# Sheet6.net
KiCad netlist of a schematic drawn in Altium Designer
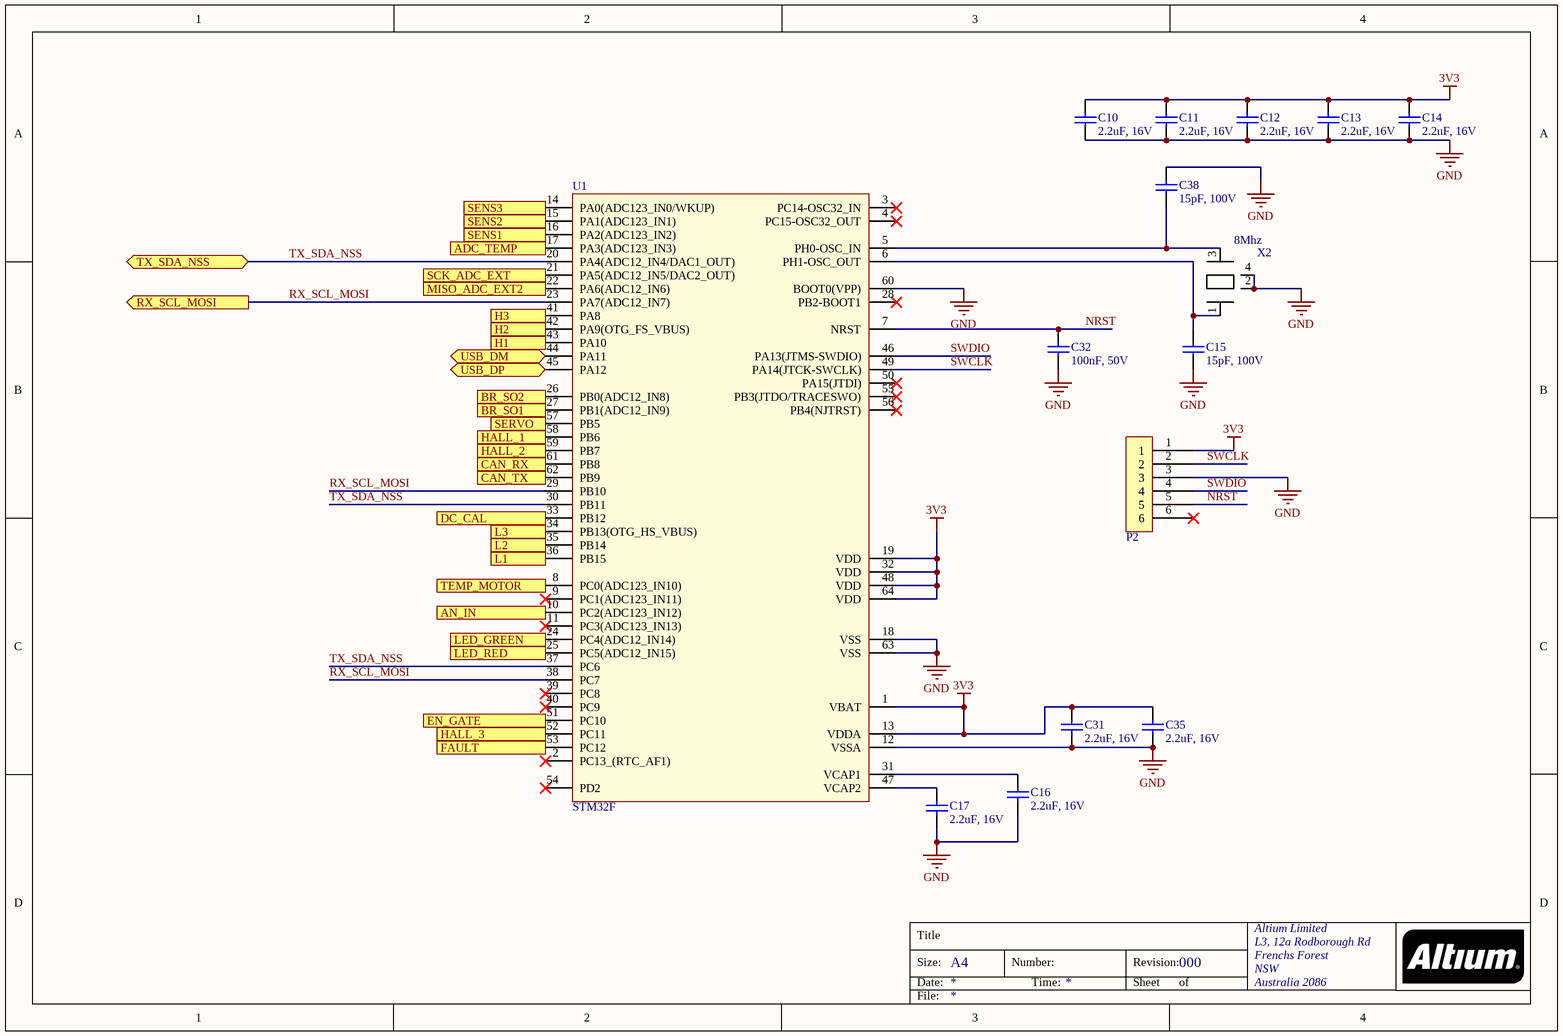
[diagram p0: Sheet6.SchDoc]

(export (version "E")
  (design (tool "Eeschema 10.0.6"))
  (components
    (comp (ref "C10")
      (value "2.2uF, 16V")
      (footprint "SMD-0603 Capacitor")
      (description "CAP 2.2u, 16V, 0603")
      (fields
        (field (name "MANUFACTURER PART NUMBER") "C1608X5R1C225M")
        (field (name "MANUFACTURER") "TDK Corporation")
      )
      (libsource (lib "Master Data Link") (part "CAP"))
    )
    (comp (ref "C11")
      (value "2.2uF, 16V")
      (footprint "SMD-0603 Capacitor")
      (description "CAP 2.2u, 16V, 0603")
      (fields
        (field (name "MANUFACTURER PART NUMBER") "C1608X5R1C225M")
        (field (name "MANUFACTURER") "TDK Corporation")
      )
      (libsource (lib "Master Data Link") (part "CAP"))
    )
    (comp (ref "C12")
      (value "2.2uF, 16V")
      (footprint "SMD-0603 Capacitor")
      (description "CAP 2.2u, 16V, 0603")
      (fields
        (field (name "MANUFACTURER PART NUMBER") "C1608X5R1C225M")
        (field (name "MANUFACTURER") "TDK Corporation")
      )
      (libsource (lib "Master Data Link") (part "CAP"))
    )
    (comp (ref "C13")
      (value "2.2uF, 16V")
      (footprint "SMD-0603 Capacitor")
      (description "CAP 2.2u, 16V, 0603")
      (fields
        (field (name "MANUFACTURER PART NUMBER") "C1608X5R1C225M")
        (field (name "MANUFACTURER") "TDK Corporation")
      )
      (libsource (lib "Master Data Link") (part "CAP"))
    )
    (comp (ref "C14")
      (value "2.2uF, 16V")
      (footprint "SMD-0603 Capacitor")
      (description "CAP 2.2u, 16V, 0603")
      (fields
        (field (name "MANUFACTURER PART NUMBER") "C1608X5R1C225M")
        (field (name "MANUFACTURER") "TDK Corporation")
      )
      (libsource (lib "Master Data Link") (part "CAP"))
    )
    (comp (ref "C15")
      (value "15pF, 100V")
      (footprint "SMD-0603 Capacitor")
      (description "CAP 15p, 100V, 0603")
      (fields
        (field (name "MANUFACTURER PART NUMBER") "GRM1885C2A150JA01")
        (field (name "MANUFACTURER") "Murata Electronics North America")
      )
      (libsource (lib "Master Data Link") (part "CAP"))
    )
    (comp (ref "C16")
      (value "2.2uF, 16V")
      (footprint "SMD-0603 Capacitor")
      (description "CAP 2.2u, 16V, 0603")
      (fields
        (field (name "MANUFACTURER PART NUMBER") "C1608X5R1C225M")
        (field (name "MANUFACTURER") "TDK Corporation")
      )
      (libsource (lib "Master Data Link") (part "CAP"))
    )
    (comp (ref "C17")
      (value "2.2uF, 16V")
      (footprint "SMD-0603 Capacitor")
      (description "CAP 2.2u, 16V, 0603")
      (fields
        (field (name "MANUFACTURER PART NUMBER") "C1608X5R1C225M")
        (field (name "MANUFACTURER") "TDK Corporation")
      )
      (libsource (lib "Master Data Link") (part "CAP"))
    )
    (comp (ref "C31")
      (value "2.2uF, 16V")
      (footprint "SMD-0603 Capacitor")
      (description "CAP 2.2u, 16V, 0603")
      (fields
        (field (name "MANUFACTURER PART NUMBER") "C1608X5R1C225M")
        (field (name "MANUFACTURER") "TDK Corporation")
      )
      (libsource (lib "Master Data Link") (part "CAP"))
    )
    (comp (ref "C32")
      (value "100nF, 50V")
      (footprint "SMD-0603 Capacitor")
      (description "CAP 100n, 50V, 0603")
      (fields
        (field (name "MANUFACTURER PART NUMBER") "06035C104JAT2A")
        (field (name "MANUFACTURER") "AVX Corporation")
      )
      (libsource (lib "Master Data Link") (part "CAP"))
    )
    (comp (ref "C35")
      (value "2.2uF, 16V")
      (footprint "SMD-0603 Capacitor")
      (description "CAP 2.2u, 16V, 0603")
      (fields
        (field (name "MANUFACTURER PART NUMBER") "C1608X5R1C225M")
        (field (name "MANUFACTURER") "TDK Corporation")
      )
      (libsource (lib "Master Data Link") (part "CAP"))
    )
    (comp (ref "C38")
      (value "15pF, 100V")
      (footprint "SMD-0603 Capacitor")
      (description "CAP 15p, 100V, 0603")
      (fields
        (field (name "MANUFACTURER PART NUMBER") "GRM1885C2A150JA01")
        (field (name "MANUFACTURER") "Murata Electronics North America")
      )
      (libsource (lib "Master Data Link") (part "CAP"))
    )
    (comp (ref "P2")
      (value "B6B-PH-K-S(LF)(SN)")
      (footprint "JST PH TH VERT 6")
      (description "JST PH Through hole Vertical 6 Pin")
      (fields (field (name "MANUFACTURER") "JST"))
      (libsource (lib "Master Data Link") (part "CON6"))
    )
    (comp (ref "U1")
      (value "STM32F")
      (footprint "TSQFP50P1200X1200X160-64")
      (description "IC MCU 32BIT 1MB FLASH 64LQFP")
      (fields
        (field (name "MANUFACTURER PART NUMBER") "STM32F405RGT6")
        (field (name "MANUFACTURER") "STMicroelectronics")
      )
      (libsource (lib "Master Data Link") (part "STM32F"))
    )
    (comp (ref "X2")
      (value "8Mhz")
      (footprint "4-SMD CRYSTAL 5X3.2mm")
      (description "Crystal 8MHz, 10PPM")
      (fields
        (field (name "MANUFACTURER PART NUMBER") "ABM3B-8.0-10-1UT")
        (field (name "MANUFACTURER") "Abracon LLC")
      )
      (libsource (lib "Master Data Link") (part "OSC_1"))
    )
  )
  (nets
    (net (code "1") (name "/ADC_TEMP") (class "Default")
      (node (ref "U1") (pin "17") (pinfunction "PA3(ADC123_IN3)_17") (pintype "passive"))
    )
    (net (code "2") (name "/AN_IN") (class "Default")
      (node (ref "U1") (pin "10") (pinfunction "PC2(ADC123_IN12)_10") (pintype "passive"))
    )
    (net (code "3") (name "/BR_SO1") (class "Default")
      (node (ref "U1") (pin "27") (pinfunction "PB1(ADC12_IN9)_27") (pintype "passive"))
    )
    (net (code "4") (name "/BR_SO2") (class "Default")
      (node (ref "U1") (pin "26") (pinfunction "PB0(ADC12_IN8)_26") (pintype "passive"))
    )
    (net (code "5") (name "/CAN_RX") (class "Default")
      (node (ref "U1") (pin "61") (pinfunction "PB8_61") (pintype "passive"))
    )
    (net (code "6") (name "/CAN_TX") (class "Default")
      (node (ref "U1") (pin "62") (pinfunction "PB9_62") (pintype "passive"))
    )
    (net (code "7") (name "/DC_CAL") (class "Default")
      (node (ref "U1") (pin "33") (pinfunction "PB12_33") (pintype "passive"))
    )
    (net (code "8") (name "/EN_GATE") (class "Default")
      (node (ref "U1") (pin "51") (pinfunction "PC10_51") (pintype "passive"))
    )
    (net (code "9") (name "/FAULT") (class "Default")
      (node (ref "U1") (pin "53") (pinfunction "PC12_53") (pintype "passive"))
    )
    (net (code "10") (name "/H1") (class "Default")
      (node (ref "U1") (pin "43") (pinfunction "PA10_43") (pintype "passive"))
    )
    (net (code "11") (name "/H2") (class "Default")
      (node (ref "U1") (pin "42") (pinfunction "PA9(OTG_FS_VBUS)_42") (pintype "passive"))
    )
    (net (code "12") (name "/H3") (class "Default")
      (node (ref "U1") (pin "41") (pinfunction "PA8_41") (pintype "passive"))
    )
    (net (code "13") (name "/HALL_1") (class "Default")
      (node (ref "U1") (pin "58") (pinfunction "PB6_58") (pintype "passive"))
    )
    (net (code "14") (name "/HALL_2") (class "Default")
      (node (ref "U1") (pin "59") (pinfunction "PB7_59") (pintype "passive"))
    )
    (net (code "15") (name "/HALL_3") (class "Default")
      (node (ref "U1") (pin "52") (pinfunction "PC11_52") (pintype "passive"))
    )
    (net (code "16") (name "/L1") (class "Default")
      (node (ref "U1") (pin "36") (pinfunction "PB15_36") (pintype "passive"))
    )
    (net (code "17") (name "/L2") (class "Default")
      (node (ref "U1") (pin "35") (pinfunction "PB14_35") (pintype "passive"))
    )
    (net (code "18") (name "/L3") (class "Default")
      (node (ref "U1") (pin "34") (pinfunction "PB13(OTG_HS_VBUS)_34") (pintype "passive"))
    )
    (net (code "19") (name "/LED_GREEN") (class "Default")
      (node (ref "U1") (pin "24") (pinfunction "PC4(ADC12_IN14)_24") (pintype "passive"))
    )
    (net (code "20") (name "/LED_RED") (class "Default")
      (node (ref "U1") (pin "25") (pinfunction "PC5(ADC12_IN15)_25") (pintype "passive"))
    )
    (net (code "21") (name "/MISO_ADC_EXT2") (class "Default")
      (node (ref "U1") (pin "22") (pinfunction "PA6(ADC12_IN6)_22") (pintype "passive"))
    )
    (net (code "22") (name "/NRST") (class "Default")
      (node (ref "C32") (pin "2") (pinfunction "2_2") (pintype "passive"))
      (node (ref "P2") (pin "5") (pinfunction "5_5") (pintype "passive"))
      (node (ref "U1") (pin "7") (pinfunction "NRST_7") (pintype "passive"))
    )
    (net (code "23") (name "/RX_SCL_MOSI") (class "Default")
      (node (ref "U1") (pin "23") (pinfunction "PA7(ADC12_IN7)_23") (pintype "passive"))
      (node (ref "U1") (pin "29") (pinfunction "PB10_29") (pintype "passive"))
      (node (ref "U1") (pin "38") (pinfunction "PC7_38") (pintype "passive"))
    )
    (net (code "24") (name "/SCK_ADC_EXT") (class "Default")
      (node (ref "U1") (pin "21") (pinfunction "PA5(ADC12_IN5/DAC2_OUT)_21") (pintype "passive"))
    )
    (net (code "25") (name "/SENS1") (class "Default")
      (node (ref "U1") (pin "16") (pinfunction "PA2(ADC123_IN2)_16") (pintype "passive"))
    )
    (net (code "26") (name "/SENS2") (class "Default")
      (node (ref "U1") (pin "15") (pinfunction "PA1(ADC123_IN1)_15") (pintype "passive"))
    )
    (net (code "27") (name "/SENS3") (class "Default")
      (node (ref "U1") (pin "14") (pinfunction "PA0(ADC123_IN0/WKUP)_14") (pintype "passive"))
    )
    (net (code "28") (name "/SERVO") (class "Default")
      (node (ref "U1") (pin "57") (pinfunction "PB5_57") (pintype "passive"))
    )
    (net (code "29") (name "/SWCLK") (class "Default")
      (node (ref "P2") (pin "2") (pinfunction "2_2") (pintype "passive"))
      (node (ref "U1") (pin "49") (pinfunction "PA14(JTCK-SWCLK)_49") (pintype "passive"))
    )
    (net (code "30") (name "/SWDIO") (class "Default")
      (node (ref "P2") (pin "4") (pinfunction "4_4") (pintype "passive"))
      (node (ref "U1") (pin "46") (pinfunction "PA13(JTMS-SWDIO)_46") (pintype "passive"))
    )
    (net (code "31") (name "/TEMP_MOTOR") (class "Default")
      (node (ref "U1") (pin "8") (pinfunction "PC0(ADC123_IN10)_8") (pintype "passive"))
    )
    (net (code "32") (name "/TX_SDA_NSS") (class "Default")
      (node (ref "U1") (pin "20") (pinfunction "PA4(ADC12_IN4/DAC1_OUT)_20") (pintype "passive"))
      (node (ref "U1") (pin "30") (pinfunction "PB11_30") (pintype "passive"))
      (node (ref "U1") (pin "37") (pinfunction "PC6_37") (pintype "passive"))
    )
    (net (code "33") (name "/USB_DM") (class "Default")
      (node (ref "U1") (pin "44") (pinfunction "PA11_44") (pintype "passive"))
    )
    (net (code "34") (name "/USB_DP") (class "Default")
      (node (ref "U1") (pin "45") (pinfunction "PA12_45") (pintype "passive"))
    )
    (net (code "35") (name "3V3") (class "Default")
      (node (ref "C10") (pin "2") (pinfunction "2_2") (pintype "passive"))
      (node (ref "C11") (pin "2") (pinfunction "2_2") (pintype "passive"))
      (node (ref "C12") (pin "2") (pinfunction "2_2") (pintype "passive"))
      (node (ref "C13") (pin "2") (pinfunction "2_2") (pintype "passive"))
      (node (ref "C14") (pin "2") (pinfunction "2_2") (pintype "passive"))
      (node (ref "C31") (pin "2") (pinfunction "2_2") (pintype "passive"))
      (node (ref "C35") (pin "2") (pinfunction "2_2") (pintype "passive"))
      (node (ref "P2") (pin "1") (pinfunction "1_1") (pintype "passive"))
      (node (ref "U1") (pin "1") (pinfunction "VBAT_1") (pintype "passive"))
      (node (ref "U1") (pin "13") (pinfunction "VDDA_13") (pintype "passive"))
      (node (ref "U1") (pin "19") (pinfunction "VDD_19") (pintype "passive"))
      (node (ref "U1") (pin "32") (pinfunction "VDD_32") (pintype "passive"))
      (node (ref "U1") (pin "48") (pinfunction "VDD_48") (pintype "passive"))
      (node (ref "U1") (pin "64") (pinfunction "VDD_64") (pintype "passive"))
    )
    (net (code "36") (name "GND") (class "Default")
      (node (ref "C10") (pin "1") (pinfunction "1_1") (pintype "passive"))
      (node (ref "C11") (pin "1") (pinfunction "1_1") (pintype "passive"))
      (node (ref "C12") (pin "1") (pinfunction "1_1") (pintype "passive"))
      (node (ref "C13") (pin "1") (pinfunction "1_1") (pintype "passive"))
      (node (ref "C14") (pin "1") (pinfunction "1_1") (pintype "passive"))
      (node (ref "C15") (pin "1") (pinfunction "1_1") (pintype "passive"))
      (node (ref "C16") (pin "1") (pinfunction "1_1") (pintype "passive"))
      (node (ref "C17") (pin "1") (pinfunction "1_1") (pintype "passive"))
      (node (ref "C31") (pin "1") (pinfunction "1_1") (pintype "passive"))
      (node (ref "C32") (pin "1") (pinfunction "1_1") (pintype "passive"))
      (node (ref "C35") (pin "1") (pinfunction "1_1") (pintype "passive"))
      (node (ref "C38") (pin "2") (pinfunction "2_2") (pintype "passive"))
      (node (ref "P2") (pin "3") (pinfunction "3_3") (pintype "passive"))
      (node (ref "U1") (pin "12") (pinfunction "VSSA_12") (pintype "passive"))
      (node (ref "U1") (pin "18") (pinfunction "VSS_18") (pintype "passive"))
      (node (ref "U1") (pin "60") (pinfunction "BOOT0(VPP)_60") (pintype "passive"))
      (node (ref "U1") (pin "63") (pinfunction "VSS_63") (pintype "passive"))
      (node (ref "X2") (pin "2") (pinfunction "3_2") (pintype "passive"))
      (node (ref "X2") (pin "4") (pinfunction "4_4") (pintype "passive"))
    )
    (net (code "37") (name "Net-(U1-PH0-OSC_IN)") (class "Default")
      (node (ref "C38") (pin "1") (pinfunction "1_1") (pintype "passive"))
      (node (ref "U1") (pin "5") (pinfunction "PH0-OSC_IN_5") (pintype "passive"))
      (node (ref "X2") (pin "3") (pinfunction "2_3") (pintype "passive"))
    )
    (net (code "38") (name "Net-(U1-PH1-OSC_OUT)") (class "Default")
      (node (ref "C15") (pin "2") (pinfunction "2_2") (pintype "passive"))
      (node (ref "U1") (pin "6") (pinfunction "PH1-OSC_OUT_6") (pintype "passive"))
      (node (ref "X2") (pin "1") (pinfunction "1_1") (pintype "passive"))
    )
    (net (code "39") (name "Net-(U1-VCAP1)") (class "Default")
      (node (ref "C16") (pin "2") (pinfunction "2_2") (pintype "passive"))
      (node (ref "U1") (pin "31") (pinfunction "VCAP1_31") (pintype "passive"))
    )
    (net (code "40") (name "Net-(U1-VCAP2)") (class "Default")
      (node (ref "C17") (pin "2") (pinfunction "2_2") (pintype "passive"))
      (node (ref "U1") (pin "47") (pinfunction "VCAP2_47") (pintype "passive"))
    )
    (net (code "41") (name "unconnected-(P2-Pad6)") (class "Default")
      (node (ref "P2") (pin "6") (pinfunction "6_6") (pintype "passive+no_connect"))
    )
    (net (code "42") (name "unconnected-(U1-PA15(JTDI)-Pad50)") (class "Default")
      (node (ref "U1") (pin "50") (pinfunction "PA15(JTDI)_50") (pintype "passive+no_connect"))
    )
    (net (code "43") (name "unconnected-(U1-PB2-BOOT1-Pad28)") (class "Default")
      (node (ref "U1") (pin "28") (pinfunction "PB2-BOOT1_28") (pintype "passive+no_connect"))
    )
    (net (code "44") (name "unconnected-(U1-PB3(JTDO{slash}TRACESWO)-Pad55)") (class "Default")
      (node (ref "U1") (pin "55") (pinfunction "PB3(JTDO/TRACESWO)_55") (pintype "passive+no_connect"))
    )
    (net (code "45") (name "unconnected-(U1-PB4(NJTRST)-Pad56)") (class "Default")
      (node (ref "U1") (pin "56") (pinfunction "PB4(NJTRST)_56") (pintype "passive+no_connect"))
    )
    (net (code "46") (name "unconnected-(U1-PC1(ADC123_IN11)-Pad9)") (class "Default")
      (node (ref "U1") (pin "9") (pinfunction "PC1(ADC123_IN11)_9") (pintype "passive+no_connect"))
    )
    (net (code "47") (name "unconnected-(U1-PC3(ADC123_IN13)-Pad11)") (class "Default")
      (node (ref "U1") (pin "11") (pinfunction "PC3(ADC123_IN13)_11") (pintype "passive+no_connect"))
    )
    (net (code "48") (name "unconnected-(U1-PC8-Pad39)") (class "Default")
      (node (ref "U1") (pin "39") (pinfunction "PC8_39") (pintype "passive+no_connect"))
    )
    (net (code "49") (name "unconnected-(U1-PC9-Pad40)") (class "Default")
      (node (ref "U1") (pin "40") (pinfunction "PC9_40") (pintype "passive+no_connect"))
    )
    (net (code "50") (name "unconnected-(U1-PC13_(RTC_AF1)-Pad2)") (class "Default")
      (node (ref "U1") (pin "2") (pinfunction "PC13_(RTC_AF1)_2") (pintype "passive+no_connect"))
    )
    (net (code "51") (name "unconnected-(U1-PC14-OSC32_IN-Pad3)") (class "Default")
      (node (ref "U1") (pin "3") (pinfunction "PC14-OSC32_IN_3") (pintype "passive+no_connect"))
    )
    (net (code "52") (name "unconnected-(U1-PC15-OSC32_OUT-Pad4)") (class "Default")
      (node (ref "U1") (pin "4") (pinfunction "PC15-OSC32_OUT_4") (pintype "passive+no_connect"))
    )
    (net (code "53") (name "unconnected-(U1-PD2-Pad54)") (class "Default")
      (node (ref "U1") (pin "54") (pinfunction "PD2_54") (pintype "passive+no_connect"))
    )
  )
)
